# i2c_adc_avr.net
KiCad netlist of a schematic drawn in EAGLE
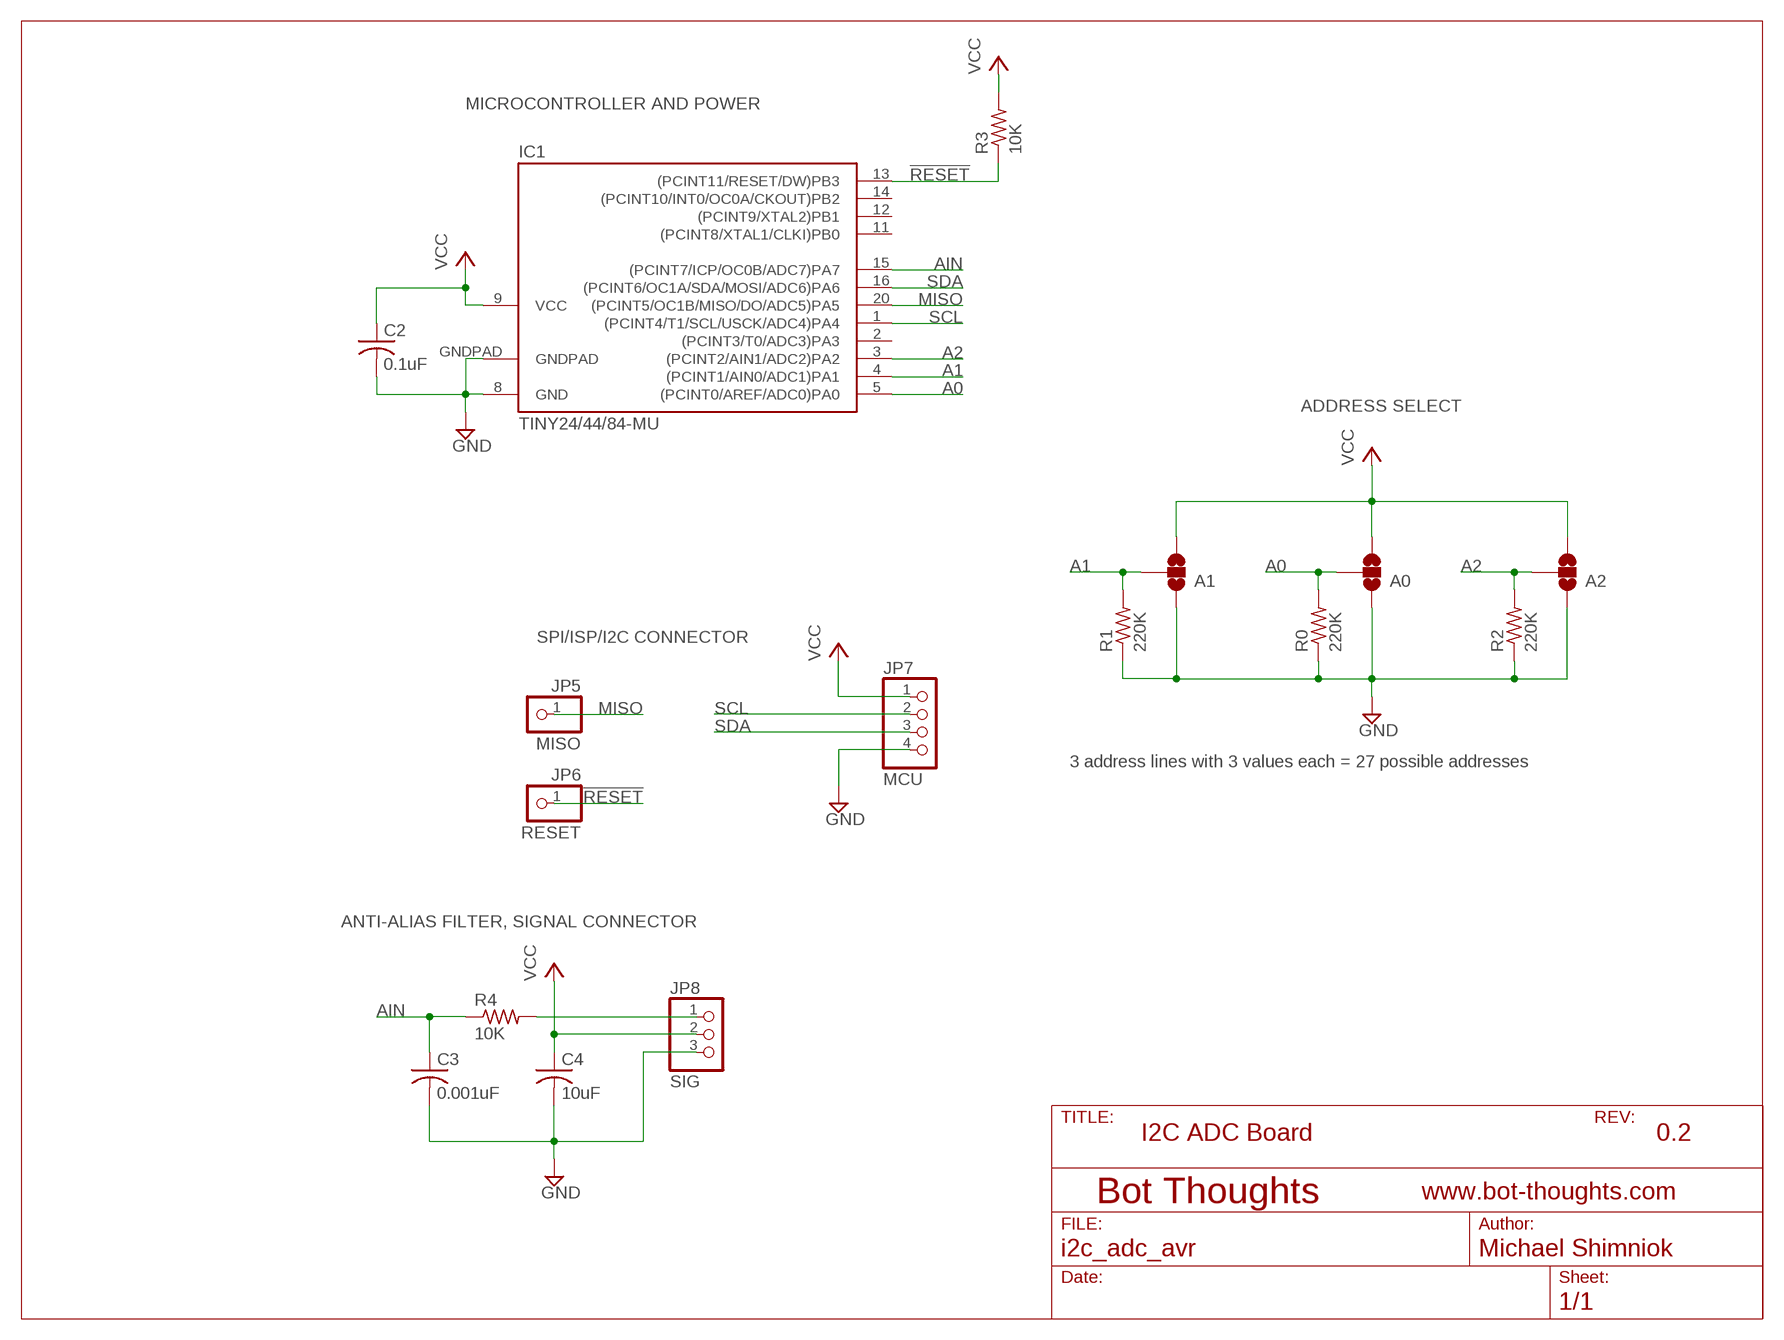
[diagram p0: schematic, sheet 1]

(export (version "E")
  (design (tool "Eeschema 10.0.6"))
  (components
    (comp (ref "A0")
      (value "SOLDERJUMPER_2WAYS")
      (footprint "eagle-import:SJ_3")
      (libsource (lib "eagle-import") (part "SOLDERJUMPER_2WAYS"))
    )
    (comp (ref "A1")
      (value "SOLDERJUMPER_2WAYS")
      (footprint "eagle-import:SJ_3")
      (libsource (lib "eagle-import") (part "SOLDERJUMPER_2WAYS"))
    )
    (comp (ref "A2")
      (value "SOLDERJUMPER_2WAYS")
      (footprint "eagle-import:SJ_3")
      (libsource (lib "eagle-import") (part "SOLDERJUMPER_2WAYS"))
    )
    (comp (ref "C2")
      (value "0.1uF")
      (footprint "eagle-import:C0603")
      (libsource (lib "eagle-import") (part "C-USC0603"))
    )
    (comp (ref "C3")
      (value "0.001uF")
      (footprint "eagle-import:C0603")
      (libsource (lib "eagle-import") (part "C-USC0603"))
    )
    (comp (ref "C4")
      (value "10uF")
      (footprint "eagle-import:C0603")
      (libsource (lib "eagle-import") (part "C-USC0603"))
    )
    (comp (ref "IC1")
      (value "TINY24/44/84-MU")
      (footprint "eagle-import:QFN_MLF20")
      (libsource (lib "eagle-import") (part "TINY24/44/84-MU"))
    )
    (comp (ref "JP5")
      (value "MISO")
      (footprint "eagle-import:1X01")
      (libsource (lib "eagle-import") (part "PINHD-1X01_2.54"))
    )
    (comp (ref "JP6")
      (value "RESET")
      (footprint "eagle-import:1X01")
      (libsource (lib "eagle-import") (part "PINHD-1X01_2.54"))
    )
    (comp (ref "JP7")
      (value "MCU")
      (footprint "eagle-import:1X04-S")
      (libsource (lib "eagle-import") (part "PINHD-1X04_2.54-S"))
    )
    (comp (ref "JP8")
      (value "SIG")
      (footprint "eagle-import:1X03M")
      (libsource (lib "eagle-import") (part "PINHD-1X03_2.00"))
    )
    (comp (ref "R0")
      (value "220K")
      (footprint "eagle-import:R0603")
      (libsource (lib "eagle-import") (part "R-US_R0603"))
    )
    (comp (ref "R1")
      (value "220K")
      (footprint "eagle-import:R0603")
      (libsource (lib "eagle-import") (part "R-US_R0603"))
    )
    (comp (ref "R2")
      (value "220K")
      (footprint "eagle-import:R0603")
      (libsource (lib "eagle-import") (part "R-US_R0603"))
    )
    (comp (ref "R3")
      (value "10K")
      (footprint "eagle-import:R0603")
      (libsource (lib "eagle-import") (part "R-US_R0603"))
    )
    (comp (ref "R4")
      (value "10K")
      (footprint "eagle-import:R0603")
      (libsource (lib "eagle-import") (part "R-US_R0603"))
    )
  )
  (nets
    (net (code "1") (name "/A0") (class "Default")
      (node (ref "A0") (pin "2") (pinfunction "2_2") (pintype "passive"))
      (node (ref "IC1") (pin "5") (pinfunction "(PCINT0/AREF/ADC0)PA0_5") (pintype "bidirectional"))
      (node (ref "R0") (pin "2") (pinfunction "2_2") (pintype "passive"))
    )
    (net (code "2") (name "/A1") (class "Default")
      (node (ref "A1") (pin "2") (pinfunction "2_2") (pintype "passive"))
      (node (ref "IC1") (pin "4") (pinfunction "(PCINT1/AIN0/ADC1)PA1_4") (pintype "bidirectional"))
      (node (ref "R1") (pin "2") (pinfunction "2_2") (pintype "passive"))
    )
    (net (code "3") (name "/A2") (class "Default")
      (node (ref "A2") (pin "2") (pinfunction "2_2") (pintype "passive"))
      (node (ref "IC1") (pin "3") (pinfunction "(PCINT2/AIN1/ADC2)PA2_3") (pintype "bidirectional"))
      (node (ref "R2") (pin "2") (pinfunction "2_2") (pintype "passive"))
    )
    (net (code "4") (name "/AIN") (class "Default")
      (node (ref "C3") (pin "1") (pinfunction "1_1") (pintype "passive"))
      (node (ref "IC1") (pin "15") (pinfunction "(PCINT7/ICP/OC0B/ADC7)PA7_15") (pintype "bidirectional"))
      (node (ref "R4") (pin "1") (pinfunction "1_1") (pintype "passive"))
    )
    (net (code "5") (name "/MISO") (class "Default")
      (node (ref "IC1") (pin "20") (pinfunction "(PCINT5/OC1B/MISO/DO/ADC5)PA5_20") (pintype "bidirectional"))
      (node (ref "JP5") (pin "1") (pinfunction "1_1") (pintype "passive"))
    )
    (net (code "6") (name "/SCL") (class "Default")
      (node (ref "IC1") (pin "1") (pinfunction "(PCINT4/T1/SCL/USCK/ADC4)PA4_1") (pintype "bidirectional"))
      (node (ref "JP7") (pin "2") (pinfunction "2_2") (pintype "passive"))
    )
    (net (code "7") (name "/SDA") (class "Default")
      (node (ref "IC1") (pin "16") (pinfunction "(PCINT6/OC1A/SDA/MOSI/ADC6)PA6_16") (pintype "bidirectional"))
      (node (ref "JP7") (pin "3") (pinfunction "3_3") (pintype "passive"))
    )
    (net (code "8") (name "/~{RESET}") (class "Default")
      (node (ref "IC1") (pin "13") (pinfunction "(PCINT11/RESET/DW)PB3_13") (pintype "bidirectional"))
      (node (ref "JP6") (pin "1") (pinfunction "1_1") (pintype "passive"))
      (node (ref "R3") (pin "1") (pinfunction "1_1") (pintype "passive"))
    )
    (net (code "9") (name "GND") (class "Default")
      (node (ref "A0") (pin "1") (pinfunction "1_1") (pintype "passive"))
      (node (ref "A1") (pin "1") (pinfunction "1_1") (pintype "passive"))
      (node (ref "A2") (pin "1") (pinfunction "1_1") (pintype "passive"))
      (node (ref "C2") (pin "2") (pinfunction "2_2") (pintype "passive"))
      (node (ref "C3") (pin "2") (pinfunction "2_2") (pintype "passive"))
      (node (ref "C4") (pin "2") (pinfunction "2_2") (pintype "passive"))
      (node (ref "IC1") (pin "8") (pinfunction "GND_8") (pintype "power_in"))
      (node (ref "IC1") (pin "GNDPAD") (pinfunction "GNDPAD_GNDPAD") (pintype "power_in"))
      (node (ref "JP7") (pin "4") (pinfunction "4_4") (pintype "passive"))
      (node (ref "JP8") (pin "3") (pinfunction "3_3") (pintype "passive"))
      (node (ref "R0") (pin "1") (pinfunction "1_1") (pintype "passive"))
      (node (ref "R1") (pin "1") (pinfunction "1_1") (pintype "passive"))
      (node (ref "R2") (pin "1") (pinfunction "1_1") (pintype "passive"))
    )
    (net (code "10") (name "Net-(JP8-Pad1)") (class "Default")
      (node (ref "JP8") (pin "1") (pinfunction "1_1") (pintype "passive"))
      (node (ref "R4") (pin "2") (pinfunction "2_2") (pintype "passive"))
    )
    (net (code "11") (name "VCC") (class "Default")
      (node (ref "A0") (pin "3") (pinfunction "3_3") (pintype "passive"))
      (node (ref "A1") (pin "3") (pinfunction "3_3") (pintype "passive"))
      (node (ref "A2") (pin "3") (pinfunction "3_3") (pintype "passive"))
      (node (ref "C2") (pin "1") (pinfunction "1_1") (pintype "passive"))
      (node (ref "C4") (pin "1") (pinfunction "1_1") (pintype "passive"))
      (node (ref "IC1") (pin "9") (pinfunction "VCC_9") (pintype "power_in"))
      (node (ref "JP7") (pin "1") (pinfunction "1_1") (pintype "passive"))
      (node (ref "JP8") (pin "2") (pinfunction "2_2") (pintype "passive"))
      (node (ref "R3") (pin "2") (pinfunction "2_2") (pintype "passive"))
    )
    (net (code "12") (name "unconnected-(IC1-(PCINT3{slash}T0{slash}ADC3)PA3-Pad2)") (class "Default")
      (node (ref "IC1") (pin "2") (pinfunction "(PCINT3/T0/ADC3)PA3_2") (pintype "bidirectional"))
    )
    (net (code "13") (name "unconnected-(IC1-(PCINT8{slash}XTAL1{slash}CLKI)PB0-Pad11)") (class "Default")
      (node (ref "IC1") (pin "11") (pinfunction "(PCINT8/XTAL1/CLKI)PB0_11") (pintype "bidirectional"))
    )
    (net (code "14") (name "unconnected-(IC1-(PCINT9{slash}XTAL2)PB1-Pad12)") (class "Default")
      (node (ref "IC1") (pin "12") (pinfunction "(PCINT9/XTAL2)PB1_12") (pintype "bidirectional"))
    )
    (net (code "15") (name "unconnected-(IC1-(PCINT10{slash}INT0{slash}OC0A{slash}CKOUT)PB2-Pad14)") (class "Default")
      (node (ref "IC1") (pin "14") (pinfunction "(PCINT10/INT0/OC0A/CKOUT)PB2_14") (pintype "bidirectional"))
    )
  )
)
